# Arduino_MEGA2560_ref.net
KiCad netlist of a schematic drawn in EAGLE
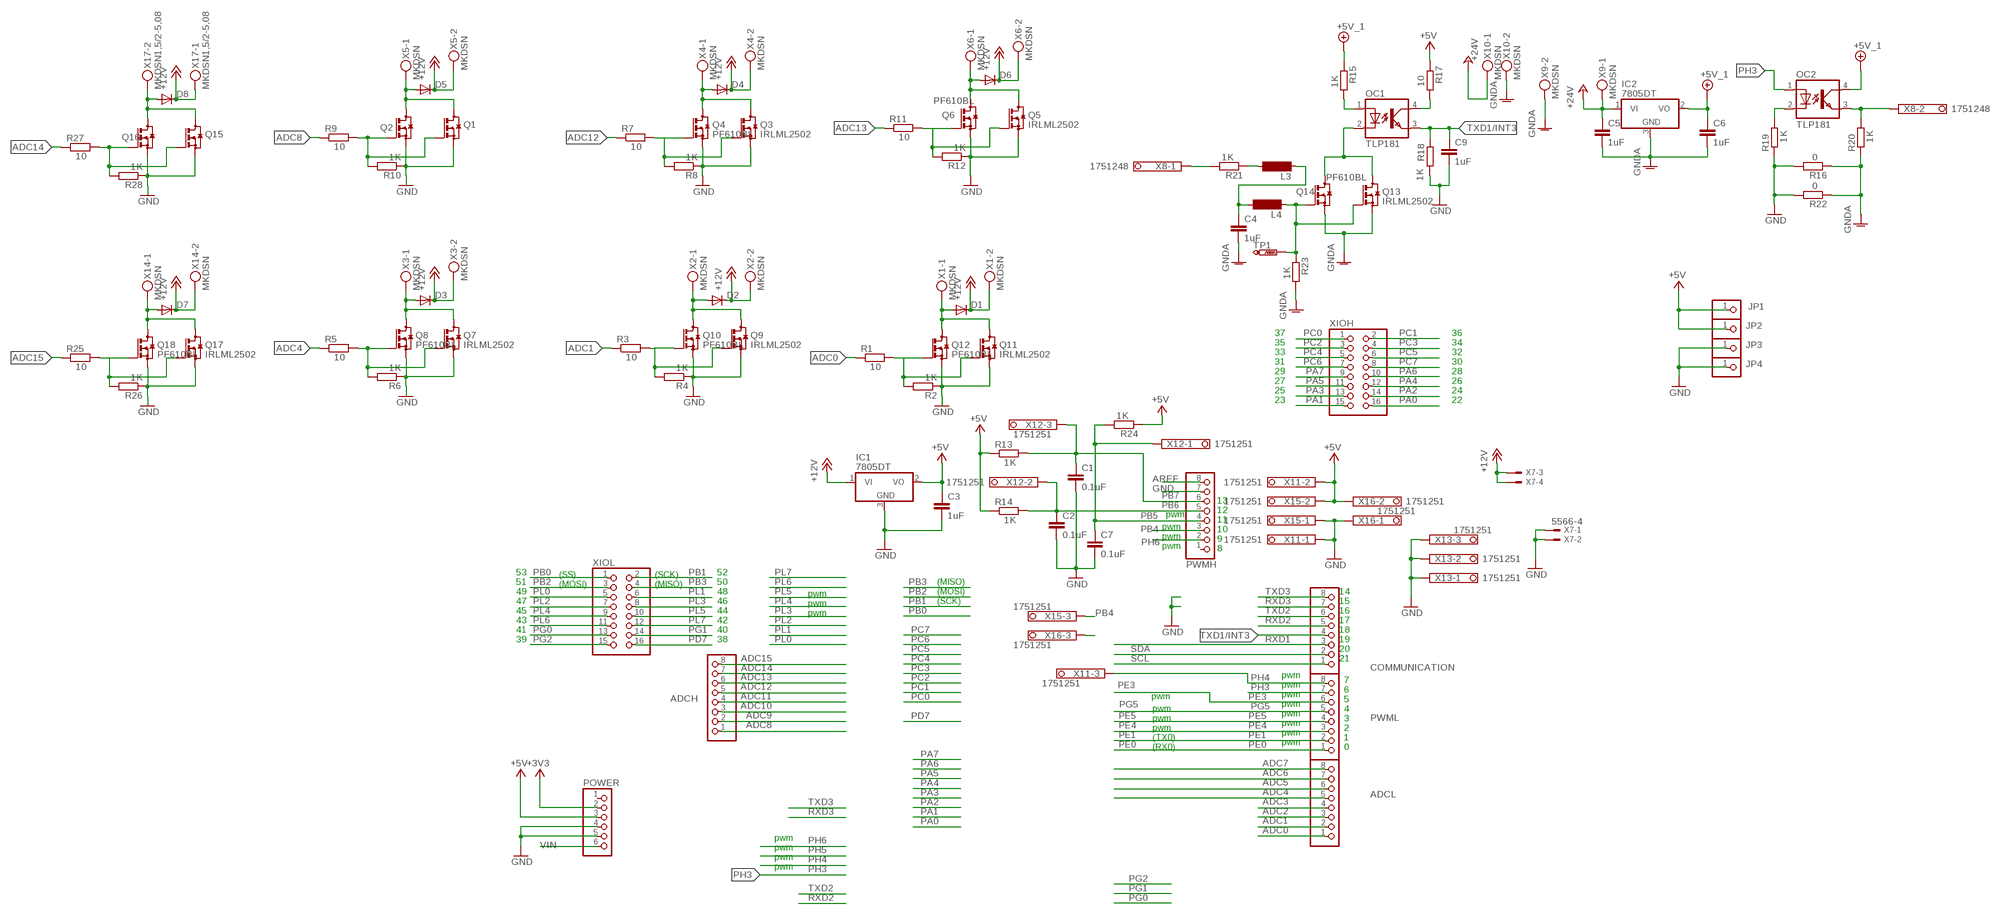
[diagram p0: schematic, sheet 1]

(export (version "E")
  (design (tool "Eeschema 10.0.6"))
  (components
    (comp (ref "ADCH")
      (value "PINHD-1X8")
      (footprint "eagle-import:1X08")
      (libsource (lib "eagle-import") (part "PINHD-1X8"))
    )
    (comp (ref "ADCL")
      (value "PINHD-1X8")
      (footprint "eagle-import:1X08")
      (libsource (lib "eagle-import") (part "PINHD-1X8"))
    )
    (comp (ref "C1")
      (value "0.1uF")
      (footprint "eagle-import:C0805")
      (libsource (lib "eagle-import") (part "C-EUC0805"))
    )
    (comp (ref "C2")
      (value "0.1uF")
      (footprint "eagle-import:C0805")
      (libsource (lib "eagle-import") (part "C-EUC0805"))
    )
    (comp (ref "C3")
      (value "1uF")
      (footprint "eagle-import:C0805")
      (libsource (lib "eagle-import") (part "C-EUC0805"))
    )
    (comp (ref "C4")
      (value "1uF")
      (footprint "eagle-import:C0805")
      (libsource (lib "eagle-import") (part "C-EUC0805"))
    )
    (comp (ref "C5")
      (value "1uF")
      (footprint "eagle-import:C0805")
      (libsource (lib "eagle-import") (part "C-EUC0805"))
    )
    (comp (ref "C6")
      (value "1uF")
      (footprint "eagle-import:C0805")
      (libsource (lib "eagle-import") (part "C-EUC0805"))
    )
    (comp (ref "C7")
      (value "0.1uF")
      (footprint "eagle-import:C0805")
      (libsource (lib "eagle-import") (part "C-EUC0805"))
    )
    (comp (ref "C9")
      (value "1uF")
      (footprint "eagle-import:C0805")
      (libsource (lib "eagle-import") (part "C-EUC0805"))
    )
    (comp (ref "COMMUNICATION")
      (value "PINHD-1X8")
      (footprint "eagle-import:1X08")
      (libsource (lib "eagle-import") (part "PINHD-1X8"))
    )
    (comp (ref "D1")
      (value "DIODE-DO214AA")
      (footprint "eagle-import:DO214AA")
      (libsource (lib "eagle-import") (part "DIODE-DO214AA"))
    )
    (comp (ref "D2")
      (value "DIODE-DO214AA")
      (footprint "eagle-import:DO214AA")
      (libsource (lib "eagle-import") (part "DIODE-DO214AA"))
    )
    (comp (ref "D3")
      (value "DIODE-DO214AA")
      (footprint "eagle-import:DO214AA")
      (libsource (lib "eagle-import") (part "DIODE-DO214AA"))
    )
    (comp (ref "D4")
      (value "DIODE-DO214AA")
      (footprint "eagle-import:DO214AA")
      (libsource (lib "eagle-import") (part "DIODE-DO214AA"))
    )
    (comp (ref "D5")
      (value "DIODE-DO214AA")
      (footprint "eagle-import:DO214AA")
      (libsource (lib "eagle-import") (part "DIODE-DO214AA"))
    )
    (comp (ref "D6")
      (value "DIODE-DO214AA")
      (footprint "eagle-import:DO214AA")
      (libsource (lib "eagle-import") (part "DIODE-DO214AA"))
    )
    (comp (ref "D7")
      (value "DIODE-DO214AA")
      (footprint "eagle-import:DO214AA")
      (libsource (lib "eagle-import") (part "DIODE-DO214AA"))
    )
    (comp (ref "D8")
      (value "DIODE-DO214AA")
      (footprint "eagle-import:DO214AA")
      (libsource (lib "eagle-import") (part "DIODE-DO214AA"))
    )
    (comp (ref "IC1")
      (value "7805DT")
      (footprint "eagle-import:TO252")
      (libsource (lib "eagle-import") (part "78DT05"))
    )
    (comp (ref "IC2")
      (value "7805DT")
      (footprint "eagle-import:TO252")
      (libsource (lib "eagle-import") (part "78DT05"))
    )
    (comp (ref "JP1")
      (value "PINHD-1X1")
      (footprint "eagle-import:1X01")
      (libsource (lib "eagle-import") (part "PINHD-1X1"))
    )
    (comp (ref "JP2")
      (value "PINHD-1X1")
      (footprint "eagle-import:1X01")
      (libsource (lib "eagle-import") (part "PINHD-1X1"))
    )
    (comp (ref "JP3")
      (value "PINHD-1X1")
      (footprint "eagle-import:1X01")
      (libsource (lib "eagle-import") (part "PINHD-1X1"))
    )
    (comp (ref "JP4")
      (value "PINHD-1X1")
      (footprint "eagle-import:1X01")
      (libsource (lib "eagle-import") (part "PINHD-1X1"))
    )
    (comp (ref "L3")
      (value "SM-NE45")
      (footprint "eagle-import:SM-NE45")
      (libsource (lib "eagle-import") (part "SM-NE45"))
    )
    (comp (ref "L4")
      (value "SM-NE45")
      (footprint "eagle-import:SM-NE45")
      (libsource (lib "eagle-import") (part "SM-NE45"))
    )
    (comp (ref "OC1")
      (value "TLP181")
      (footprint "eagle-import:SO-4")
      (libsource (lib "eagle-import") (part "TLP181"))
    )
    (comp (ref "OC2")
      (value "TLP181")
      (footprint "eagle-import:SO-4")
      (libsource (lib "eagle-import") (part "TLP181"))
    )
    (comp (ref "POWER")
      (value "PINHD-1X6")
      (footprint "eagle-import:1X06")
      (libsource (lib "eagle-import") (part "PINHD-1X6"))
    )
    (comp (ref "PWMH")
      (value "PINHD-1X8")
      (footprint "eagle-import:1X08")
      (libsource (lib "eagle-import") (part "PINHD-1X8"))
    )
    (comp (ref "PWML")
      (value "PINHD-1X8")
      (footprint "eagle-import:1X08")
      (libsource (lib "eagle-import") (part "PINHD-1X8"))
    )
    (comp (ref "Q1")
      (value "IRLML2502")
      (footprint "eagle-import:SOT23")
      (libsource (lib "eagle-import") (part "IRLML2502"))
    )
    (comp (ref "Q2")
      (value "PF610BL")
      (footprint "eagle-import:SOT223")
      (libsource (lib "eagle-import") (part "PF610BL"))
    )
    (comp (ref "Q3")
      (value "IRLML2502")
      (footprint "eagle-import:SOT23")
      (libsource (lib "eagle-import") (part "IRLML2502"))
    )
    (comp (ref "Q4")
      (value "PF610BL")
      (footprint "eagle-import:SOT223")
      (libsource (lib "eagle-import") (part "PF610BL"))
    )
    (comp (ref "Q5")
      (value "IRLML2502")
      (footprint "eagle-import:SOT23")
      (libsource (lib "eagle-import") (part "IRLML2502"))
    )
    (comp (ref "Q6")
      (value "PF610BL")
      (footprint "eagle-import:SOT223")
      (libsource (lib "eagle-import") (part "PF610BL"))
    )
    (comp (ref "Q7")
      (value "IRLML2502")
      (footprint "eagle-import:SOT23")
      (libsource (lib "eagle-import") (part "IRLML2502"))
    )
    (comp (ref "Q8")
      (value "PF610BL")
      (footprint "eagle-import:SOT223")
      (libsource (lib "eagle-import") (part "PF610BL"))
    )
    (comp (ref "Q9")
      (value "IRLML2502")
      (footprint "eagle-import:SOT23")
      (libsource (lib "eagle-import") (part "IRLML2502"))
    )
    (comp (ref "Q10")
      (value "PF610BL")
      (footprint "eagle-import:SOT223")
      (libsource (lib "eagle-import") (part "PF610BL"))
    )
    (comp (ref "Q11")
      (value "IRLML2502")
      (footprint "eagle-import:SOT23")
      (libsource (lib "eagle-import") (part "IRLML2502"))
    )
    (comp (ref "Q12")
      (value "PF610BL")
      (footprint "eagle-import:SOT223")
      (libsource (lib "eagle-import") (part "PF610BL"))
    )
    (comp (ref "Q13")
      (value "IRLML2502")
      (footprint "eagle-import:SOT23")
      (libsource (lib "eagle-import") (part "IRLML2502"))
    )
    (comp (ref "Q14")
      (value "PF610BL")
      (footprint "eagle-import:SOT223")
      (libsource (lib "eagle-import") (part "PF610BL"))
    )
    (comp (ref "Q15")
      (value "IRLML2502")
      (footprint "eagle-import:SOT23")
      (libsource (lib "eagle-import") (part "IRLML2502"))
    )
    (comp (ref "Q16")
      (value "PF610BL")
      (footprint "eagle-import:SOT223")
      (libsource (lib "eagle-import") (part "PF610BL"))
    )
    (comp (ref "Q17")
      (value "IRLML2502")
      (footprint "eagle-import:SOT23")
      (libsource (lib "eagle-import") (part "IRLML2502"))
    )
    (comp (ref "Q18")
      (value "PF610BL")
      (footprint "eagle-import:SOT223")
      (libsource (lib "eagle-import") (part "PF610BL"))
    )
    (comp (ref "R1")
      (value "10")
      (footprint "eagle-import:M0805")
      (libsource (lib "eagle-import") (part "R-EU_M0805"))
    )
    (comp (ref "R2")
      (value "1K")
      (footprint "eagle-import:M0805")
      (libsource (lib "eagle-import") (part "R-EU_M0805"))
    )
    (comp (ref "R3")
      (value "10")
      (footprint "eagle-import:M0805")
      (libsource (lib "eagle-import") (part "R-EU_M0805"))
    )
    (comp (ref "R4")
      (value "1K")
      (footprint "eagle-import:M0805")
      (libsource (lib "eagle-import") (part "R-EU_M0805"))
    )
    (comp (ref "R5")
      (value "10")
      (footprint "eagle-import:M0805")
      (libsource (lib "eagle-import") (part "R-EU_M0805"))
    )
    (comp (ref "R6")
      (value "1K")
      (footprint "eagle-import:M0805")
      (libsource (lib "eagle-import") (part "R-EU_M0805"))
    )
    (comp (ref "R7")
      (value "10")
      (footprint "eagle-import:M0805")
      (libsource (lib "eagle-import") (part "R-EU_M0805"))
    )
    (comp (ref "R8")
      (value "1K")
      (footprint "eagle-import:M0805")
      (libsource (lib "eagle-import") (part "R-EU_M0805"))
    )
    (comp (ref "R9")
      (value "10")
      (footprint "eagle-import:M0805")
      (libsource (lib "eagle-import") (part "R-EU_M0805"))
    )
    (comp (ref "R10")
      (value "1K")
      (footprint "eagle-import:M0805")
      (libsource (lib "eagle-import") (part "R-EU_M0805"))
    )
    (comp (ref "R11")
      (value "10")
      (footprint "eagle-import:M0805")
      (libsource (lib "eagle-import") (part "R-EU_M0805"))
    )
    (comp (ref "R12")
      (value "1K")
      (footprint "eagle-import:M0805")
      (libsource (lib "eagle-import") (part "R-EU_M0805"))
    )
    (comp (ref "R13")
      (value "1K")
      (footprint "eagle-import:M0805")
      (libsource (lib "eagle-import") (part "R-EU_M0805"))
    )
    (comp (ref "R14")
      (value "1K")
      (footprint "eagle-import:M0805")
      (libsource (lib "eagle-import") (part "R-EU_M0805"))
    )
    (comp (ref "R15")
      (value "1K")
      (footprint "eagle-import:M0805")
      (libsource (lib "eagle-import") (part "R-EU_M0805"))
    )
    (comp (ref "R16")
      (value "0")
      (footprint "eagle-import:M0805")
      (libsource (lib "eagle-import") (part "R-EU_M0805"))
    )
    (comp (ref "R17")
      (value "10")
      (footprint "eagle-import:M0805")
      (libsource (lib "eagle-import") (part "R-EU_M0805"))
    )
    (comp (ref "R18")
      (value "1K")
      (footprint "eagle-import:M0805")
      (libsource (lib "eagle-import") (part "R-EU_M0805"))
    )
    (comp (ref "R19")
      (value "1K")
      (footprint "eagle-import:M0805")
      (libsource (lib "eagle-import") (part "R-EU_M0805"))
    )
    (comp (ref "R20")
      (value "1K")
      (footprint "eagle-import:M0805")
      (libsource (lib "eagle-import") (part "R-EU_M0805"))
    )
    (comp (ref "R21")
      (value "1K")
      (footprint "eagle-import:M0805")
      (libsource (lib "eagle-import") (part "R-EU_M0805"))
    )
    (comp (ref "R22")
      (value "0")
      (footprint "eagle-import:M0805")
      (libsource (lib "eagle-import") (part "R-EU_M0805"))
    )
    (comp (ref "R23")
      (value "1K")
      (footprint "eagle-import:M0805")
      (libsource (lib "eagle-import") (part "R-EU_M0805"))
    )
    (comp (ref "R24")
      (value "1K")
      (footprint "eagle-import:M0805")
      (libsource (lib "eagle-import") (part "R-EU_M0805"))
    )
    (comp (ref "R25")
      (value "10")
      (footprint "eagle-import:M0805")
      (libsource (lib "eagle-import") (part "R-EU_M0805"))
    )
    (comp (ref "R26")
      (value "1K")
      (footprint "eagle-import:M0805")
      (libsource (lib "eagle-import") (part "R-EU_M0805"))
    )
    (comp (ref "R27")
      (value "10")
      (footprint "eagle-import:M0805")
      (libsource (lib "eagle-import") (part "R-EU_M0805"))
    )
    (comp (ref "R28")
      (value "1K")
      (footprint "eagle-import:M0805")
      (libsource (lib "eagle-import") (part "R-EU_M0805"))
    )
    (comp (ref "TP1")
      (value "PTR1TP20SQ")
      (footprint "eagle-import:TP20SQ")
      (libsource (lib "eagle-import") (part "PTR1TP20SQ"))
    )
    (comp (ref "X1")
      (value "MKDSN")
      (footprint "eagle-import:MKDSN1,5_2-5,08")
      (libsource (lib "eagle-import") (part "MKDSN1,5/2-5,08"))
    )
    (comp (ref "X2")
      (value "MKDSN")
      (footprint "eagle-import:MKDSN1,5_2-5,08")
      (libsource (lib "eagle-import") (part "MKDSN1,5/2-5,08"))
    )
    (comp (ref "X3")
      (value "MKDSN")
      (footprint "eagle-import:MKDSN1,5_2-5,08")
      (libsource (lib "eagle-import") (part "MKDSN1,5/2-5,08"))
    )
    (comp (ref "X4")
      (value "MKDSN")
      (footprint "eagle-import:MKDSN1,5_2-5,08")
      (libsource (lib "eagle-import") (part "MKDSN1,5/2-5,08"))
    )
    (comp (ref "X5")
      (value "MKDSN")
      (footprint "eagle-import:MKDSN1,5_2-5,08")
      (libsource (lib "eagle-import") (part "MKDSN1,5/2-5,08"))
    )
    (comp (ref "X6")
      (value "MKDSN")
      (footprint "eagle-import:MKDSN1,5_2-5,08")
      (libsource (lib "eagle-import") (part "MKDSN1,5/2-5,08"))
    )
    (comp (ref "X7")
      (value "5566-4")
      (footprint "eagle-import:5566-4")
      (libsource (lib "eagle-import") (part "5566-4"))
    )
    (comp (ref "X8")
      (value "1751248")
      (footprint "eagle-import:1751248")
      (libsource (lib "eagle-import") (part "1751248"))
    )
    (comp (ref "X9")
      (value "MKDSN")
      (footprint "eagle-import:MKDSN1,5_2-5,08")
      (libsource (lib "eagle-import") (part "MKDSN1,5/2-5,08"))
    )
    (comp (ref "X10")
      (value "MKDSN")
      (footprint "eagle-import:MKDSN1,5_2-5,08")
      (libsource (lib "eagle-import") (part "MKDSN1,5/2-5,08"))
    )
    (comp (ref "X11")
      (value "1751251")
      (footprint "eagle-import:1751251")
      (libsource (lib "eagle-import") (part "1751251"))
    )
    (comp (ref "X12")
      (value "1751251")
      (footprint "eagle-import:1751251")
      (libsource (lib "eagle-import") (part "1751251"))
    )
    (comp (ref "X13")
      (value "1751251")
      (footprint "eagle-import:1751251")
      (libsource (lib "eagle-import") (part "1751251"))
    )
    (comp (ref "X14")
      (value "MKDSN")
      (footprint "eagle-import:MKDSN1,5_2-5,08")
      (libsource (lib "eagle-import") (part "MKDSN1,5/2-5,08"))
    )
    (comp (ref "X15")
      (value "1751251")
      (footprint "eagle-import:1751251")
      (libsource (lib "eagle-import") (part "1751251"))
    )
    (comp (ref "X16")
      (value "1751251")
      (footprint "eagle-import:1751251")
      (libsource (lib "eagle-import") (part "1751251"))
    )
    (comp (ref "X17")
      (value "MKDSN1,5/2-5,08")
      (footprint "eagle-import:MKDSN1,5_2-5,08")
      (libsource (lib "eagle-import") (part "MKDSN1,5/2-5,08"))
    )
    (comp (ref "XIOH")
      (value "PINHD-2X8")
      (footprint "eagle-import:2X08")
      (libsource (lib "eagle-import") (part "PINHD-2X8"))
    )
    (comp (ref "XIOL")
      (value "PINHD-2X8")
      (footprint "eagle-import:2X08")
      (libsource (lib "eagle-import") (part "PINHD-2X8"))
    )
  )
  (nets
    (net (code "1") (name "+3V3") (class "Default")
      (node (ref "POWER") (pin "2") (pinfunction "2_2") (pintype "passive"))
    )
    (net (code "2") (name "+5V") (class "Default")
      (node (ref "C3") (pin "1") (pinfunction "1_1") (pintype "passive"))
      (node (ref "IC1") (pin "2") (pinfunction "VO_2") (pintype "passive"))
      (node (ref "JP1") (pin "1") (pinfunction "1_1") (pintype "passive"))
      (node (ref "JP2") (pin "1") (pinfunction "1_1") (pintype "passive"))
      (node (ref "POWER") (pin "3") (pinfunction "3_3") (pintype "passive"))
      (node (ref "R13") (pin "1") (pinfunction "1_1") (pintype "passive"))
      (node (ref "R14") (pin "1") (pinfunction "1_1") (pintype "passive"))
      (node (ref "R17") (pin "1") (pinfunction "1_1") (pintype "passive"))
      (node (ref "R24") (pin "1") (pinfunction "1_1") (pintype "passive"))
      (node (ref "X11") (pin "2") (pinfunction "K_2") (pintype "passive"))
      (node (ref "X15") (pin "2") (pinfunction "K_2") (pintype "passive"))
      (node (ref "X16") (pin "2") (pinfunction "K_2") (pintype "passive"))
    )
    (net (code "3") (name "+5V_1") (class "Default")
      (node (ref "C6") (pin "1") (pinfunction "1_1") (pintype "passive"))
      (node (ref "IC2") (pin "2") (pinfunction "VO_2") (pintype "passive"))
      (node (ref "OC2") (pin "4") (pinfunction "COL_4") (pintype "passive"))
      (node (ref "R15") (pin "1") (pinfunction "1_1") (pintype "passive"))
    )
    (net (code "4") (name "+12V") (class "Default")
      (node (ref "D1") (pin "C") (pinfunction "C_C") (pintype "passive"))
      (node (ref "D2") (pin "C") (pinfunction "C_C") (pintype "passive"))
      (node (ref "D3") (pin "C") (pinfunction "C_C") (pintype "passive"))
      (node (ref "D4") (pin "C") (pinfunction "C_C") (pintype "passive"))
      (node (ref "D5") (pin "C") (pinfunction "C_C") (pintype "passive"))
      (node (ref "D6") (pin "C") (pinfunction "C_C") (pintype "passive"))
      (node (ref "D7") (pin "C") (pinfunction "C_C") (pintype "passive"))
      (node (ref "D8") (pin "C") (pinfunction "C_C") (pintype "passive"))
      (node (ref "IC1") (pin "1") (pinfunction "VI_1") (pintype "input"))
      (node (ref "X1") (pin "2") (pinfunction "KL_2") (pintype "passive"))
      (node (ref "X14") (pin "2") (pinfunction "KL_2") (pintype "passive"))
      (node (ref "X17") (pin "1") (pinfunction "KL_1") (pintype "passive"))
      (node (ref "X2") (pin "2") (pinfunction "KL_2") (pintype "passive"))
      (node (ref "X3") (pin "2") (pinfunction "KL_2") (pintype "passive"))
      (node (ref "X4") (pin "2") (pinfunction "KL_2") (pintype "passive"))
      (node (ref "X5") (pin "2") (pinfunction "KL_2") (pintype "passive"))
      (node (ref "X6") (pin "2") (pinfunction "KL_2") (pintype "passive"))
      (node (ref "X7") (pin "3") (pinfunction "S_3") (pintype "passive"))
      (node (ref "X7") (pin "4") (pinfunction "S_4") (pintype "passive"))
    )
    (net (code "5") (name "+24V") (class "Default")
      (node (ref "C5") (pin "1") (pinfunction "1_1") (pintype "passive"))
      (node (ref "IC2") (pin "1") (pinfunction "VI_1") (pintype "input"))
      (node (ref "X10") (pin "1") (pinfunction "KL_1") (pintype "passive"))
      (node (ref "X9") (pin "1") (pinfunction "KL_1") (pintype "passive"))
    )
    (net (code "6") (name "/ADC2") (class "Default")
      (node (ref "ADCL") (pin "3") (pinfunction "3_3") (pintype "passive"))
    )
    (net (code "7") (name "/ADC3") (class "Default")
      (node (ref "ADCL") (pin "4") (pinfunction "4_4") (pintype "passive"))
    )
    (net (code "8") (name "/ADC5") (class "Default")
      (node (ref "ADCL") (pin "6") (pinfunction "6_6") (pintype "passive"))
    )
    (net (code "9") (name "/ADC6") (class "Default")
      (node (ref "ADCL") (pin "7") (pinfunction "7_7") (pintype "passive"))
    )
    (net (code "10") (name "/ADC7") (class "Default")
      (node (ref "ADCL") (pin "8") (pinfunction "8_8") (pintype "passive"))
    )
    (net (code "11") (name "/ADC9") (class "Default")
      (node (ref "ADCH") (pin "2") (pinfunction "2_2") (pintype "passive"))
    )
    (net (code "12") (name "/ADC10") (class "Default")
      (node (ref "ADCH") (pin "3") (pinfunction "3_3") (pintype "passive"))
    )
    (net (code "13") (name "/ADC11") (class "Default")
      (node (ref "ADCH") (pin "4") (pinfunction "4_4") (pintype "passive"))
    )
    (net (code "14") (name "/AREF") (class "Default")
      (node (ref "PWMH") (pin "8") (pinfunction "8_8") (pintype "passive"))
    )
    (net (code "15") (name "/PA0") (class "Default")
      (node (ref "XIOH") (pin "16") (pinfunction "16_16") (pintype "passive"))
    )
    (net (code "16") (name "/PA1") (class "Default")
      (node (ref "XIOH") (pin "15") (pinfunction "15_15") (pintype "passive"))
    )
    (net (code "17") (name "/PA2") (class "Default")
      (node (ref "XIOH") (pin "14") (pinfunction "14_14") (pintype "passive"))
    )
    (net (code "18") (name "/PA3") (class "Default")
      (node (ref "XIOH") (pin "13") (pinfunction "13_13") (pintype "passive"))
    )
    (net (code "19") (name "/PA4") (class "Default")
      (node (ref "XIOH") (pin "12") (pinfunction "12_12") (pintype "passive"))
    )
    (net (code "20") (name "/PA5") (class "Default")
      (node (ref "XIOH") (pin "11") (pinfunction "11_11") (pintype "passive"))
    )
    (net (code "21") (name "/PA6") (class "Default")
      (node (ref "XIOH") (pin "10") (pinfunction "10_10") (pintype "passive"))
    )
    (net (code "22") (name "/PA7") (class "Default")
      (node (ref "XIOH") (pin "9") (pinfunction "9_9") (pintype "passive"))
    )
    (net (code "23") (name "/PB0") (class "Default")
      (node (ref "XIOL") (pin "1") (pinfunction "1_1") (pintype "passive"))
    )
    (net (code "24") (name "/PB1") (class "Default")
      (node (ref "XIOL") (pin "2") (pinfunction "2_2") (pintype "passive"))
    )
    (net (code "25") (name "/PB2") (class "Default")
      (node (ref "XIOL") (pin "3") (pinfunction "3_3") (pintype "passive"))
    )
    (net (code "26") (name "/PB3") (class "Default")
      (node (ref "XIOL") (pin "4") (pinfunction "4_4") (pintype "passive"))
    )
    (net (code "27") (name "/PB4") (class "Default")
      (node (ref "PWMH") (pin "3") (pinfunction "3_3") (pintype "passive"))
      (node (ref "X15") (pin "3") (pinfunction "K_3") (pintype "passive"))
    )
    (net (code "28") (name "/PB5") (class "Default")
      (node (ref "C7") (pin "1") (pinfunction "1_1") (pintype "passive"))
      (node (ref "PWMH") (pin "4") (pinfunction "4_4") (pintype "passive"))
      (node (ref "R24") (pin "2") (pinfunction "2_2") (pintype "passive"))
      (node (ref "X12") (pin "1") (pinfunction "K_1") (pintype "passive"))
    )
    (net (code "29") (name "/PB6") (class "Default")
      (node (ref "C2") (pin "1") (pinfunction "1_1") (pintype "passive"))
      (node (ref "PWMH") (pin "5") (pinfunction "5_5") (pintype "passive"))
      (node (ref "R14") (pin "2") (pinfunction "2_2") (pintype "passive"))
      (node (ref "X12") (pin "2") (pinfunction "K_2") (pintype "passive"))
    )
    (net (code "30") (name "/PB7") (class "Default")
      (node (ref "C1") (pin "1") (pinfunction "1_1") (pintype "passive"))
      (node (ref "PWMH") (pin "6") (pinfunction "6_6") (pintype "passive"))
      (node (ref "R13") (pin "2") (pinfunction "2_2") (pintype "passive"))
      (node (ref "X12") (pin "3") (pinfunction "K_3") (pintype "passive"))
    )
    (net (code "31") (name "/PC0") (class "Default")
      (node (ref "XIOH") (pin "1") (pinfunction "1_1") (pintype "passive"))
    )
    (net (code "32") (name "/PC1") (class "Default")
      (node (ref "XIOH") (pin "2") (pinfunction "2_2") (pintype "passive"))
    )
    (net (code "33") (name "/PC2") (class "Default")
      (node (ref "XIOH") (pin "3") (pinfunction "3_3") (pintype "passive"))
    )
    (net (code "34") (name "/PC3") (class "Default")
      (node (ref "XIOH") (pin "4") (pinfunction "4_4") (pintype "passive"))
    )
    (net (code "35") (name "/PC4") (class "Default")
      (node (ref "XIOH") (pin "5") (pinfunction "5_5") (pintype "passive"))
    )
    (net (code "36") (name "/PC5") (class "Default")
      (node (ref "XIOH") (pin "6") (pinfunction "6_6") (pintype "passive"))
    )
    (net (code "37") (name "/PC6") (class "Default")
      (node (ref "XIOH") (pin "7") (pinfunction "7_7") (pintype "passive"))
    )
    (net (code "38") (name "/PC7") (class "Default")
      (node (ref "XIOH") (pin "8") (pinfunction "8_8") (pintype "passive"))
    )
    (net (code "39") (name "/PD7") (class "Default")
      (node (ref "XIOL") (pin "16") (pinfunction "16_16") (pintype "passive"))
    )
    (net (code "40") (name "/PE0") (class "Default")
      (node (ref "PWML") (pin "1") (pinfunction "1_1") (pintype "passive"))
    )
    (net (code "41") (name "/PE1") (class "Default")
      (node (ref "PWML") (pin "2") (pinfunction "2_2") (pintype "passive"))
    )
    (net (code "42") (name "/PE3") (class "Default")
      (node (ref "PWML") (pin "6") (pinfunction "6_6") (pintype "passive"))
    )
    (net (code "43") (name "/PE4") (class "Default")
      (node (ref "PWML") (pin "3") (pinfunction "3_3") (pintype "passive"))
    )
    (net (code "44") (name "/PE5") (class "Default")
      (node (ref "PWML") (pin "4") (pinfunction "4_4") (pintype "passive"))
    )
    (net (code "45") (name "/PG0") (class "Default")
      (node (ref "XIOL") (pin "13") (pinfunction "13_13") (pintype "passive"))
    )
    (net (code "46") (name "/PG1") (class "Default")
      (node (ref "XIOL") (pin "14") (pinfunction "14_14") (pintype "passive"))
    )
    (net (code "47") (name "/PG2") (class "Default")
      (node (ref "XIOL") (pin "15") (pinfunction "15_15") (pintype "passive"))
    )
    (net (code "48") (name "/PG5") (class "Default")
      (node (ref "PWML") (pin "5") (pinfunction "5_5") (pintype "passive"))
    )
    (net (code "49") (name "/PH4") (class "Default")
      (node (ref "PWML") (pin "8") (pinfunction "8_8") (pintype "passive"))
      (node (ref "X11") (pin "3") (pinfunction "K_3") (pintype "passive"))
    )
    (net (code "51") (name "/PH6") (class "Default")
      (node (ref "PWMH") (pin "2") (pinfunction "2_2") (pintype "passive"))
      (node (ref "X16") (pin "3") (pinfunction "K_3") (pintype "passive"))
    )
    (net (code "52") (name "/PL0") (class "Default")
      (node (ref "XIOL") (pin "5") (pinfunction "5_5") (pintype "passive"))
    )
    (net (code "53") (name "/PL1") (class "Default")
      (node (ref "XIOL") (pin "6") (pinfunction "6_6") (pintype "passive"))
    )
    (net (code "54") (name "/PL2") (class "Default")
      (node (ref "XIOL") (pin "7") (pinfunction "7_7") (pintype "passive"))
    )
    (net (code "55") (name "/PL3") (class "Default")
      (node (ref "XIOL") (pin "8") (pinfunction "8_8") (pintype "passive"))
    )
    (net (code "56") (name "/PL4") (class "Default")
      (node (ref "XIOL") (pin "9") (pinfunction "9_9") (pintype "passive"))
    )
    (net (code "57") (name "/PL5") (class "Default")
      (node (ref "XIOL") (pin "10") (pinfunction "10_10") (pintype "passive"))
    )
    (net (code "58") (name "/PL6") (class "Default")
      (node (ref "XIOL") (pin "11") (pinfunction "11_11") (pintype "passive"))
    )
    (net (code "59") (name "/PL7") (class "Default")
      (node (ref "XIOL") (pin "12") (pinfunction "12_12") (pintype "passive"))
    )
    (net (code "60") (name "/RXD1") (class "Default")
      (node (ref "COMMUNICATION") (pin "3") (pinfunction "3_3") (pintype "passive"))
    )
    (net (code "61") (name "/RXD2") (class "Default")
      (node (ref "COMMUNICATION") (pin "5") (pinfunction "5_5") (pintype "passive"))
    )
    (net (code "62") (name "/RXD3") (class "Default")
      (node (ref "COMMUNICATION") (pin "7") (pinfunction "7_7") (pintype "passive"))
    )
    (net (code "63") (name "/SCL") (class "Default")
      (node (ref "COMMUNICATION") (pin "1") (pinfunction "1_1") (pintype "passive"))
    )
    (net (code "64") (name "/SDA") (class "Default")
      (node (ref "COMMUNICATION") (pin "2") (pinfunction "2_2") (pintype "passive"))
    )
    (net (code "65") (name "/TXD2") (class "Default")
      (node (ref "COMMUNICATION") (pin "6") (pinfunction "6_6") (pintype "passive"))
    )
    (net (code "66") (name "/TXD3") (class "Default")
      (node (ref "COMMUNICATION") (pin "8") (pinfunction "8_8") (pintype "passive"))
    )
    (net (code "67") (name "/VIN") (class "Default")
      (node (ref "POWER") (pin "6") (pinfunction "6_6") (pintype "passive"))
    )
    (net (code "68") (name "ADC0") (class "Default")
      (node (ref "ADCL") (pin "1") (pinfunction "1_1") (pintype "passive"))
      (node (ref "R1") (pin "1") (pinfunction "1_1") (pintype "passive"))
    )
    (net (code "69") (name "ADC1") (class "Default")
      (node (ref "ADCL") (pin "2") (pinfunction "2_2") (pintype "passive"))
      (node (ref "R3") (pin "1") (pinfunction "1_1") (pintype "passive"))
    )
    (net (code "70") (name "ADC4") (class "Default")
      (node (ref "ADCL") (pin "5") (pinfunction "5_5") (pintype "passive"))
      (node (ref "R5") (pin "1") (pinfunction "1_1") (pintype "passive"))
    )
    (net (code "71") (name "ADC8") (class "Default")
      (node (ref "ADCH") (pin "1") (pinfunction "1_1") (pintype "passive"))
      (node (ref "R9") (pin "1") (pinfunction "1_1") (pintype "passive"))
    )
    (net (code "72") (name "ADC12") (class "Default")
      (node (ref "ADCH") (pin "5") (pinfunction "5_5") (pintype "passive"))
      (node (ref "R7") (pin "1") (pinfunction "1_1") (pintype "passive"))
    )
    (net (code "73") (name "ADC13") (class "Default")
      (node (ref "ADCH") (pin "6") (pinfunction "6_6") (pintype "passive"))
      (node (ref "R11") (pin "1") (pinfunction "1_1") (pintype "passive"))
    )
    (net (code "74") (name "ADC14") (class "Default")
      (node (ref "ADCH") (pin "7") (pinfunction "7_7") (pintype "passive"))
      (node (ref "R27") (pin "1") (pinfunction "1_1") (pintype "passive"))
    )
    (net (code "75") (name "ADC15") (class "Default")
      (node (ref "ADCH") (pin "8") (pinfunction "8_8") (pintype "passive"))
      (node (ref "R25") (pin "1") (pinfunction "1_1") (pintype "passive"))
    )
    (net (code "76") (name "GND") (class "Default")
      (node (ref "C1") (pin "2") (pinfunction "2_2") (pintype "passive"))
      (node (ref "C2") (pin "2") (pinfunction "2_2") (pintype "passive"))
      (node (ref "C3") (pin "2") (pinfunction "2_2") (pintype "passive"))
      (node (ref "C7") (pin "2") (pinfunction "2_2") (pintype "passive"))
      (node (ref "C9") (pin "2") (pinfunction "2_2") (pintype "passive"))
      (node (ref "IC1") (pin "3") (pinfunction "GND_3") (pintype "passive"))
      (node (ref "JP3") (pin "1") (pinfunction "1_1") (pintype "passive"))
      (node (ref "JP4") (pin "1") (pinfunction "1_1") (pintype "passive"))
      (node (ref "POWER") (pin "4") (pinfunction "4_4") (pintype "passive"))
      (node (ref "POWER") (pin "5") (pinfunction "5_5") (pintype "passive"))
      (node (ref "PWMH") (pin "7") (pinfunction "7_7") (pintype "passive"))
      (node (ref "Q1") (pin "S") (pinfunction "S_S") (pintype "passive"))
      (node (ref "Q10") (pin "S") (pinfunction "S_S") (pintype "passive"))
      (node (ref "Q11") (pin "S") (pinfunction "S_S") (pintype "passive"))
      (node (ref "Q12") (pin "S") (pinfunction "S_S") (pintype "passive"))
      (node (ref "Q15") (pin "S") (pinfunction "S_S") (pintype "passive"))
      (node (ref "Q16") (pin "S") (pinfunction "S_S") (pintype "passive"))
      (node (ref "Q17") (pin "S") (pinfunction "S_S") (pintype "passive"))
      (node (ref "Q18") (pin "S") (pinfunction "S_S") (pintype "passive"))
      (node (ref "Q2") (pin "S") (pinfunction "S_S") (pintype "passive"))
      (node (ref "Q3") (pin "S") (pinfunction "S_S") (pintype "passive"))
      (node (ref "Q4") (pin "S") (pinfunction "S_S") (pintype "passive"))
      (node (ref "Q5") (pin "S") (pinfunction "S_S") (pintype "passive"))
      (node (ref "Q6") (pin "S") (pinfunction "S_S") (pintype "passive"))
      (node (ref "Q7") (pin "S") (pinfunction "S_S") (pintype "passive"))
      (node (ref "Q8") (pin "S") (pinfunction "S_S") (pintype "passive"))
      (node (ref "Q9") (pin "S") (pinfunction "S_S") (pintype "passive"))
      (node (ref "R10") (pin "1") (pinfunction "1_1") (pintype "passive"))
      (node (ref "R12") (pin "1") (pinfunction "1_1") (pintype "passive"))
      (node (ref "R16") (pin "2") (pinfunction "2_2") (pintype "passive"))
      (node (ref "R18") (pin "1") (pinfunction "1_1") (pintype "passive"))
      (node (ref "R19") (pin "1") (pinfunction "1_1") (pintype "passive"))
      (node (ref "R2") (pin "1") (pinfunction "1_1") (pintype "passive"))
      (node (ref "R22") (pin "2") (pinfunction "2_2") (pintype "passive"))
      (node (ref "R26") (pin "1") (pinfunction "1_1") (pintype "passive"))
      (node (ref "R28") (pin "1") (pinfunction "1_1") (pintype "passive"))
      (node (ref "R4") (pin "1") (pinfunction "1_1") (pintype "passive"))
      (node (ref "R6") (pin "1") (pinfunction "1_1") (pintype "passive"))
      (node (ref "R8") (pin "1") (pinfunction "1_1") (pintype "passive"))
      (node (ref "X11") (pin "1") (pinfunction "K_1") (pintype "passive"))
      (node (ref "X13") (pin "1") (pinfunction "K_1") (pintype "passive"))
      (node (ref "X13") (pin "2") (pinfunction "K_2") (pintype "passive"))
      (node (ref "X13") (pin "3") (pinfunction "K_3") (pintype "passive"))
      (node (ref "X15") (pin "1") (pinfunction "K_1") (pintype "passive"))
      (node (ref "X16") (pin "1") (pinfunction "K_1") (pintype "passive"))
      (node (ref "X7") (pin "1") (pinfunction "S_1") (pintype "passive"))
      (node (ref "X7") (pin "2") (pinfunction "S_2") (pintype "passive"))
    )
    (net (code "77") (name "GNDA") (class "Default")
      (node (ref "C4") (pin "2") (pinfunction "2_2") (pintype "passive"))
      (node (ref "C5") (pin "2") (pinfunction "2_2") (pintype "passive"))
      (node (ref "C6") (pin "2") (pinfunction "2_2") (pintype "passive"))
      (node (ref "IC2") (pin "3") (pinfunction "GND_3") (pintype "passive"))
      (node (ref "Q13") (pin "S") (pinfunction "S_S") (pintype "passive"))
      (node (ref "Q14") (pin "S") (pinfunction "S_S") (pintype "passive"))
      (node (ref "R16") (pin "1") (pinfunction "1_1") (pintype "passive"))
      (node (ref "R20") (pin "1") (pinfunction "1_1") (pintype "passive"))
      (node (ref "R22") (pin "1") (pinfunction "1_1") (pintype "passive"))
      (node (ref "R23") (pin "2") (pinfunction "2_2") (pintype "passive"))
      (node (ref "X10") (pin "2") (pinfunction "KL_2") (pintype "passive"))
      (node (ref "X9") (pin "2") (pinfunction "KL_2") (pintype "passive"))
    )
    (net (code "78") (name "Net-(C4-Pad1)") (class "Default")
      (node (ref "C4") (pin "1") (pinfunction "1_1") (pintype "passive"))
      (node (ref "L3") (pin "1") (pinfunction "1_1") (pintype "passive"))
      (node (ref "L4") (pin "2") (pinfunction "2_2") (pintype "passive"))
    )
    (net (code "79") (name "Net-(L3-Pad2)") (class "Default")
      (node (ref "L3") (pin "2") (pinfunction "2_2") (pintype "passive"))
      (node (ref "R21") (pin "1") (pinfunction "1_1") (pintype "passive"))
    )
    (net (code "80") (name "Net-(L4-Pad1)") (class "Default")
      (node (ref "L4") (pin "1") (pinfunction "1_1") (pintype "passive"))
      (node (ref "Q13") (pin "G") (pinfunction "G_G") (pintype "passive"))
      (node (ref "Q14") (pin "G") (pinfunction "G_G") (pintype "passive"))
      (node (ref "R23") (pin "1") (pinfunction "1_1") (pintype "passive"))
      (node (ref "TP1") (pin "TP") (pinfunction "TP_TP") (pintype "input"))
    )
    (net (code "81") (name "Net-(OC1-A)") (class "Default")
      (node (ref "OC1") (pin "1") (pinfunction "A_1") (pintype "passive"))
      (node (ref "R15") (pin "2") (pinfunction "2_2") (pintype "passive"))
    )
    (net (code "82") (name "Net-(OC1-C)") (class "Default")
      (node (ref "OC1") (pin "2") (pinfunction "C_2") (pintype "passive"))
      (node (ref "Q13") (pin "D") (pinfunction "D_D") (pintype "passive"))
      (node (ref "Q14") (pin "D") (pinfunction "D_D") (pintype "passive"))
      (node (ref "Q14") (pin "D_TAB") (pinfunction "D_D_TAB") (pintype "passive"))
    )
    (net (code "83") (name "Net-(OC1-COL)") (class "Default")
      (node (ref "OC1") (pin "4") (pinfunction "COL_4") (pintype "passive"))
      (node (ref "R17") (pin "2") (pinfunction "2_2") (pintype "passive"))
    )
    (net (code "84") (name "Net-(OC2-C)") (class "Default")
      (node (ref "OC2") (pin "2") (pinfunction "C_2") (pintype "passive"))
      (node (ref "R19") (pin "2") (pinfunction "2_2") (pintype "passive"))
    )
    (net (code "85") (name "Net-(OC2-EMIT)") (class "Default")
      (node (ref "OC2") (pin "3") (pinfunction "EMIT_3") (pintype "passive"))
      (node (ref "R20") (pin "2") (pinfunction "2_2") (pintype "passive"))
      (node (ref "X8") (pin "2") (pinfunction "K_2") (pintype "passive"))
    )
    (net (code "86") (name "Net-(Q1-PadG)") (class "Default")
      (node (ref "Q1") (pin "G") (pinfunction "G_G") (pintype "passive"))
      (node (ref "Q2") (pin "G") (pinfunction "G_G") (pintype "passive"))
      (node (ref "R10") (pin "2") (pinfunction "2_2") (pintype "passive"))
      (node (ref "R9") (pin "2") (pinfunction "2_2") (pintype "passive"))
    )
    (net (code "87") (name "Net-(Q3-PadG)") (class "Default")
      (node (ref "Q3") (pin "G") (pinfunction "G_G") (pintype "passive"))
      (node (ref "Q4") (pin "G") (pinfunction "G_G") (pintype "passive"))
      (node (ref "R7") (pin "2") (pinfunction "2_2") (pintype "passive"))
      (node (ref "R8") (pin "2") (pinfunction "2_2") (pintype "passive"))
    )
    (net (code "88") (name "Net-(Q5-PadG)") (class "Default")
      (node (ref "Q5") (pin "G") (pinfunction "G_G") (pintype "passive"))
      (node (ref "Q6") (pin "G") (pinfunction "G_G") (pintype "passive"))
      (node (ref "R11") (pin "2") (pinfunction "2_2") (pintype "passive"))
      (node (ref "R12") (pin "2") (pinfunction "2_2") (pintype "passive"))
    )
    (net (code "89") (name "Net-(Q7-PadG)") (class "Default")
      (node (ref "Q7") (pin "G") (pinfunction "G_G") (pintype "passive"))
      (node (ref "Q8") (pin "G") (pinfunction "G_G") (pintype "passive"))
      (node (ref "R5") (pin "2") (pinfunction "2_2") (pintype "passive"))
      (node (ref "R6") (pin "2") (pinfunction "2_2") (pintype "passive"))
    )
    (net (code "90") (name "Net-(Q10-PadG)") (class "Default")
      (node (ref "Q10") (pin "G") (pinfunction "G_G") (pintype "passive"))
      (node (ref "Q9") (pin "G") (pinfunction "G_G") (pintype "passive"))
      (node (ref "R3") (pin "2") (pinfunction "2_2") (pintype "passive"))
      (node (ref "R4") (pin "2") (pinfunction "2_2") (pintype "passive"))
    )
    (net (code "91") (name "Net-(Q11-PadG)") (class "Default")
      (node (ref "Q11") (pin "G") (pinfunction "G_G") (pintype "passive"))
      (node (ref "Q12") (pin "G") (pinfunction "G_G") (pintype "passive"))
      (node (ref "R1") (pin "2") (pinfunction "2_2") (pintype "passive"))
      (node (ref "R2") (pin "2") (pinfunction "2_2") (pintype "passive"))
    )
    (net (code "92") (name "Net-(Q15-PadG)") (class "Default")
      (node (ref "Q15") (pin "G") (pinfunction "G_G") (pintype "passive"))
      (node (ref "Q16") (pin "G") (pinfunction "G_G") (pintype "passive"))
      (node (ref "R27") (pin "2") (pinfunction "2_2") (pintype "passive"))
      (node (ref "R28") (pin "2") (pinfunction "2_2") (pintype "passive"))
    )
    (net (code "93") (name "Net-(Q17-PadG)") (class "Default")
      (node (ref "Q17") (pin "G") (pinfunction "G_G") (pintype "passive"))
      (node (ref "Q18") (pin "G") (pinfunction "G_G") (pintype "passive"))
      (node (ref "R25") (pin "2") (pinfunction "2_2") (pintype "passive"))
      (node (ref "R26") (pin "2") (pinfunction "2_2") (pintype "passive"))
    )
    (net (code "94") (name "Net-(X1A-KL)") (class "Default")
      (node (ref "D1") (pin "A") (pinfunction "A_A") (pintype "passive"))
      (node (ref "Q11") (pin "D") (pinfunction "D_D") (pintype "passive"))
      (node (ref "Q12") (pin "D") (pinfunction "D_D") (pintype "passive"))
      (node (ref "Q12") (pin "D_TAB") (pinfunction "D_D_TAB") (pintype "passive"))
      (node (ref "X1") (pin "1") (pinfunction "KL_1") (pintype "passive"))
    )
    (net (code "95") (name "Net-(X2A-KL)") (class "Default")
      (node (ref "D2") (pin "A") (pinfunction "A_A") (pintype "passive"))
      (node (ref "Q10") (pin "D") (pinfunction "D_D") (pintype "passive"))
      (node (ref "Q10") (pin "D_TAB") (pinfunction "D_D_TAB") (pintype "passive"))
      (node (ref "Q9") (pin "D") (pinfunction "D_D") (pintype "passive"))
      (node (ref "X2") (pin "1") (pinfunction "KL_1") (pintype "passive"))
    )
    (net (code "96") (name "Net-(X3A-KL)") (class "Default")
      (node (ref "D3") (pin "A") (pinfunction "A_A") (pintype "passive"))
      (node (ref "Q7") (pin "D") (pinfunction "D_D") (pintype "passive"))
      (node (ref "Q8") (pin "D") (pinfunction "D_D") (pintype "passive"))
      (node (ref "Q8") (pin "D_TAB") (pinfunction "D_D_TAB") (pintype "passive"))
      (node (ref "X3") (pin "1") (pinfunction "KL_1") (pintype "passive"))
    )
    (net (code "97") (name "Net-(X4A-KL)") (class "Default")
      (node (ref "D4") (pin "A") (pinfunction "A_A") (pintype "passive"))
      (node (ref "Q3") (pin "D") (pinfunction "D_D") (pintype "passive"))
      (node (ref "Q4") (pin "D") (pinfunction "D_D") (pintype "passive"))
      (node (ref "Q4") (pin "D_TAB") (pinfunction "D_D_TAB") (pintype "passive"))
      (node (ref "X4") (pin "1") (pinfunction "KL_1") (pintype "passive"))
    )
    (net (code "98") (name "Net-(X5A-KL)") (class "Default")
      (node (ref "D5") (pin "A") (pinfunction "A_A") (pintype "passive"))
      (node (ref "Q1") (pin "D") (pinfunction "D_D") (pintype "passive"))
      (node (ref "Q2") (pin "D") (pinfunction "D_D") (pintype "passive"))
      (node (ref "Q2") (pin "D_TAB") (pinfunction "D_D_TAB") (pintype "passive"))
      (node (ref "X5") (pin "1") (pinfunction "KL_1") (pintype "passive"))
    )
    (net (code "99") (name "Net-(X6A-KL)") (class "Default")
      (node (ref "D6") (pin "A") (pinfunction "A_A") (pintype "passive"))
      (node (ref "Q5") (pin "D") (pinfunction "D_D") (pintype "passive"))
      (node (ref "Q6") (pin "D") (pinfunction "D_D") (pintype "passive"))
      (node (ref "Q6") (pin "D_TAB") (pinfunction "D_D_TAB") (pintype "passive"))
      (node (ref "X6") (pin "1") (pinfunction "KL_1") (pintype "passive"))
    )
    (net (code "100") (name "Net-(X8A-K)") (class "Default")
      (node (ref "R21") (pin "2") (pinfunction "2_2") (pintype "passive"))
      (node (ref "X8") (pin "1") (pinfunction "K_1") (pintype "passive"))
    )
    (net (code "101") (name "Net-(X14A-KL)") (class "Default")
      (node (ref "D7") (pin "A") (pinfunction "A_A") (pintype "passive"))
      (node (ref "Q17") (pin "D") (pinfunction "D_D") (pintype "passive"))
      (node (ref "Q18") (pin "D") (pinfunction "D_D") (pintype "passive"))
      (node (ref "Q18") (pin "D_TAB") (pinfunction "D_D_TAB") (pintype "passive"))
      (node (ref "X14") (pin "1") (pinfunction "KL_1") (pintype "passive"))
    )
    (net (code "102") (name "Net-(X17B-KL)") (class "Default")
      (node (ref "D8") (pin "A") (pinfunction "A_A") (pintype "passive"))
      (node (ref "Q15") (pin "D") (pinfunction "D_D") (pintype "passive"))
      (node (ref "Q16") (pin "D") (pinfunction "D_D") (pintype "passive"))
      (node (ref "Q16") (pin "D_TAB") (pinfunction "D_D_TAB") (pintype "passive"))
      (node (ref "X17") (pin "2") (pinfunction "KL_2") (pintype "passive"))
    )
    (net (code "103") (name "PH3") (class "Default")
      (node (ref "OC2") (pin "1") (pinfunction "A_1") (pintype "passive"))
      (node (ref "PWML") (pin "7") (pinfunction "7_7") (pintype "passive"))
    )
    (net (code "104") (name "TXD1{slash}INT3") (class "Default")
      (node (ref "C9") (pin "1") (pinfunction "1_1") (pintype "passive"))
      (node (ref "COMMUNICATION") (pin "4") (pinfunction "4_4") (pintype "passive"))
      (node (ref "OC1") (pin "3") (pinfunction "EMIT_3") (pintype "passive"))
      (node (ref "R18") (pin "2") (pinfunction "2_2") (pintype "passive"))
    )
    (net (code "105") (name "unconnected-(POWER-Pad1)") (class "Default")
      (node (ref "POWER") (pin "1") (pinfunction "1_1") (pintype "passive"))
    )
    (net (code "106") (name "unconnected-(PWMH-Pad1)") (class "Default")
      (node (ref "PWMH") (pin "1") (pinfunction "1_1") (pintype "passive"))
    )
  )
)
